# bluetooth.net
KiCad netlist of a schematic drawn in Altium Designer
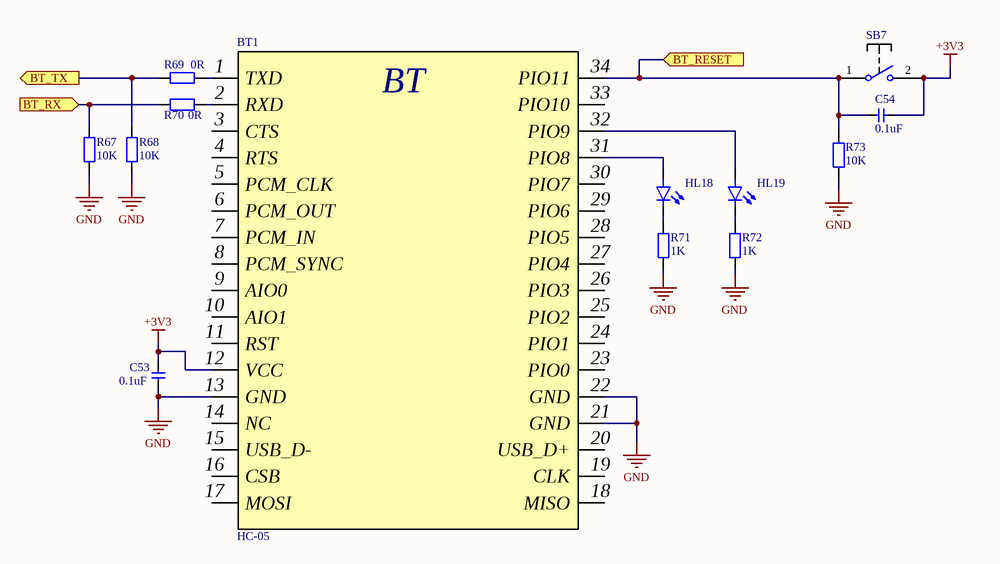
[diagram p0: bluetooth.SchDoc]

(export (version "E")
  (design (tool "Eeschema 10.0.6"))
  (components
    (comp (ref "BT1")
      (value "HC-05")
      (footprint "HC-05")
      (description "Bluetooth")
      (libsource (lib "Asterisk") (part "HC-05"))
    )
    (comp (ref "C53")
      (value "0.1uF")
      (footprint "CAP0805")
      (description "Ceramic SMD Cap")
      (libsource (lib "Asterisk") (part "CAP Ceramic"))
    )
    (comp (ref "C54")
      (value "0.1uF")
      (footprint "CAP0805")
      (description "Ceramic SMD Cap")
      (libsource (lib "Asterisk") (part "CAP Ceramic"))
    )
    (comp (ref "HL18")
      (value "White")
      (footprint "LED0603_WHITE")
      (description "SMD LED")
      (libsource (lib "Asterisk") (part "LED"))
    )
    (comp (ref "HL19")
      (value "White")
      (footprint "LED0603_WHITE")
      (description "SMD LED")
      (libsource (lib "Asterisk") (part "LED"))
    )
    (comp (ref "R67")
      (value "10K")
      (footprint "RES0805")
      (description "RES smd")
      (libsource (lib "Asterisk") (part "RES"))
    )
    (comp (ref "R68")
      (value "10K")
      (footprint "RES0805")
      (description "RES smd")
      (libsource (lib "Asterisk") (part "RES"))
    )
    (comp (ref "R69")
      (value "0R")
      (footprint "RES0805")
      (description "RES smd")
      (libsource (lib "Asterisk") (part "RES"))
    )
    (comp (ref "R70")
      (value "0R")
      (footprint "RES0805")
      (description "RES smd")
      (libsource (lib "Asterisk") (part "RES"))
    )
    (comp (ref "R71")
      (value "1K")
      (footprint "RES0805")
      (description "RES smd")
      (libsource (lib "Asterisk") (part "RES"))
    )
    (comp (ref "R72")
      (value "1K")
      (footprint "RES0805")
      (description "RES smd")
      (libsource (lib "Asterisk") (part "RES"))
    )
    (comp (ref "R73")
      (value "10K")
      (footprint "RES0805")
      (description "RES smd")
      (libsource (lib "Asterisk") (part "RES"))
    )
    (comp (ref "SB7")
      (value "TACT 6.0 X 3.5")
      (footprint "PTS636 SP43 LFS")
      (description "Button")
      (fields
        (field (name "PART NUMBER") "PTS636 SP43 LFS")
        (field (name "DIGI-KEY PART NUMBER") "CKN12304-ND")
      )
      (libsource (lib "SssAccesDatbase") (part "SW-SPST"))
    )
  )
  (nets
    (net (code "1") (name "+3V3") (class "Default")
      (node (ref "BT1") (pin "12") (pinfunction "VCC_12") (pintype "passive"))
      (node (ref "C53") (pin "2") (pinfunction "2_2") (pintype "passive"))
      (node (ref "C54") (pin "1") (pinfunction "1_1") (pintype "passive"))
      (node (ref "SB7") (pin "2") (pinfunction "NO_2") (pintype "passive"))
    )
    (net (code "2") (name "/BT_RESET") (class "Default")
      (node (ref "BT1") (pin "34") (pinfunction "PIO11_34") (pintype "passive"))
      (node (ref "C54") (pin "2") (pinfunction "2_2") (pintype "passive"))
      (node (ref "R73") (pin "2") (pinfunction "2_2") (pintype "passive"))
      (node (ref "SB7") (pin "1") (pinfunction "COMMON_1") (pintype "passive"))
    )
    (net (code "3") (name "/BT_RX") (class "Default")
      (node (ref "R67") (pin "2") (pinfunction "2_2") (pintype "passive"))
      (node (ref "R70") (pin "2") (pinfunction "2_2") (pintype "passive"))
    )
    (net (code "4") (name "/BT_TX") (class "Default")
      (node (ref "R68") (pin "2") (pinfunction "2_2") (pintype "passive"))
      (node (ref "R69") (pin "2") (pinfunction "2_2") (pintype "passive"))
    )
    (net (code "5") (name "GND") (class "Default")
      (node (ref "BT1") (pin "13") (pinfunction "GND_13") (pintype "passive"))
      (node (ref "BT1") (pin "21") (pinfunction "GND_21") (pintype "passive"))
      (node (ref "BT1") (pin "22") (pinfunction "GND_22") (pintype "passive"))
      (node (ref "C53") (pin "1") (pinfunction "1_1") (pintype "passive"))
      (node (ref "R67") (pin "1") (pinfunction "1_1") (pintype "passive"))
      (node (ref "R68") (pin "1") (pinfunction "1_1") (pintype "passive"))
      (node (ref "R71") (pin "1") (pinfunction "1_1") (pintype "passive"))
      (node (ref "R72") (pin "1") (pinfunction "1_1") (pintype "passive"))
      (node (ref "R73") (pin "1") (pinfunction "1_1") (pintype "passive"))
    )
    (net (code "6") (name "Net-(BT1-PIO8)") (class "Default")
      (node (ref "BT1") (pin "31") (pinfunction "PIO8_31") (pintype "passive"))
      (node (ref "HL18") (pin "2") (pinfunction "A_2") (pintype "passive"))
    )
    (net (code "7") (name "Net-(BT1-PIO9)") (class "Default")
      (node (ref "BT1") (pin "32") (pinfunction "PIO9_32") (pintype "passive"))
      (node (ref "HL19") (pin "2") (pinfunction "A_2") (pintype "passive"))
    )
    (net (code "8") (name "Net-(BT1-RXD)") (class "Default")
      (node (ref "BT1") (pin "2") (pinfunction "RXD_2") (pintype "passive"))
      (node (ref "R70") (pin "1") (pinfunction "1_1") (pintype "passive"))
    )
    (net (code "9") (name "Net-(BT1-TXD)") (class "Default")
      (node (ref "BT1") (pin "1") (pinfunction "TXD_1") (pintype "passive"))
      (node (ref "R69") (pin "1") (pinfunction "1_1") (pintype "passive"))
    )
    (net (code "10") (name "Net-(HL18-K)") (class "Default")
      (node (ref "HL18") (pin "1") (pinfunction "K_1") (pintype "passive"))
      (node (ref "R71") (pin "2") (pinfunction "2_2") (pintype "passive"))
    )
    (net (code "11") (name "Net-(HL19-K)") (class "Default")
      (node (ref "HL19") (pin "1") (pinfunction "K_1") (pintype "passive"))
      (node (ref "R72") (pin "2") (pinfunction "2_2") (pintype "passive"))
    )
    (net (code "12") (name "unconnected-(BT1-AIO0-Pad9)") (class "Default")
      (node (ref "BT1") (pin "9") (pinfunction "AIO0_9") (pintype "passive"))
    )
    (net (code "13") (name "unconnected-(BT1-AIO1-Pad10)") (class "Default")
      (node (ref "BT1") (pin "10") (pinfunction "AIO1_10") (pintype "passive"))
    )
    (net (code "14") (name "unconnected-(BT1-CLK-Pad19)") (class "Default")
      (node (ref "BT1") (pin "19") (pinfunction "CLK_19") (pintype "passive"))
    )
    (net (code "15") (name "unconnected-(BT1-CSB-Pad16)") (class "Default")
      (node (ref "BT1") (pin "16") (pinfunction "CSB_16") (pintype "passive"))
    )
    (net (code "16") (name "unconnected-(BT1-CTS-Pad3)") (class "Default")
      (node (ref "BT1") (pin "3") (pinfunction "CTS_3") (pintype "passive"))
    )
    (net (code "17") (name "unconnected-(BT1-MISO-Pad18)") (class "Default")
      (node (ref "BT1") (pin "18") (pinfunction "MISO_18") (pintype "passive"))
    )
    (net (code "18") (name "unconnected-(BT1-MOSI-Pad17)") (class "Default")
      (node (ref "BT1") (pin "17") (pinfunction "MOSI_17") (pintype "passive"))
    )
    (net (code "19") (name "unconnected-(BT1-NC-Pad14)") (class "Default")
      (node (ref "BT1") (pin "14") (pinfunction "NC_14") (pintype "passive"))
    )
    (net (code "20") (name "unconnected-(BT1-PCM_CLK-Pad5)") (class "Default")
      (node (ref "BT1") (pin "5") (pinfunction "PCM_CLK_5") (pintype "passive"))
    )
    (net (code "21") (name "unconnected-(BT1-PCM_IN-Pad7)") (class "Default")
      (node (ref "BT1") (pin "7") (pinfunction "PCM_IN_7") (pintype "passive"))
    )
    (net (code "22") (name "unconnected-(BT1-PCM_OUT-Pad6)") (class "Default")
      (node (ref "BT1") (pin "6") (pinfunction "PCM_OUT_6") (pintype "passive"))
    )
    (net (code "23") (name "unconnected-(BT1-PCM_SYNC-Pad8)") (class "Default")
      (node (ref "BT1") (pin "8") (pinfunction "PCM_SYNC_8") (pintype "passive"))
    )
    (net (code "24") (name "unconnected-(BT1-PIO0-Pad23)") (class "Default")
      (node (ref "BT1") (pin "23") (pinfunction "PIO0_23") (pintype "passive"))
    )
    (net (code "25") (name "unconnected-(BT1-PIO1-Pad24)") (class "Default")
      (node (ref "BT1") (pin "24") (pinfunction "PIO1_24") (pintype "passive"))
    )
    (net (code "26") (name "unconnected-(BT1-PIO2-Pad25)") (class "Default")
      (node (ref "BT1") (pin "25") (pinfunction "PIO2_25") (pintype "passive"))
    )
    (net (code "27") (name "unconnected-(BT1-PIO3-Pad26)") (class "Default")
      (node (ref "BT1") (pin "26") (pinfunction "PIO3_26") (pintype "passive"))
    )
    (net (code "28") (name "unconnected-(BT1-PIO4-Pad27)") (class "Default")
      (node (ref "BT1") (pin "27") (pinfunction "PIO4_27") (pintype "passive"))
    )
    (net (code "29") (name "unconnected-(BT1-PIO5-Pad28)") (class "Default")
      (node (ref "BT1") (pin "28") (pinfunction "PIO5_28") (pintype "passive"))
    )
    (net (code "30") (name "unconnected-(BT1-PIO6-Pad29)") (class "Default")
      (node (ref "BT1") (pin "29") (pinfunction "PIO6_29") (pintype "passive"))
    )
    (net (code "31") (name "unconnected-(BT1-PIO7-Pad30)") (class "Default")
      (node (ref "BT1") (pin "30") (pinfunction "PIO7_30") (pintype "passive"))
    )
    (net (code "32") (name "unconnected-(BT1-PIO10-Pad33)") (class "Default")
      (node (ref "BT1") (pin "33") (pinfunction "PIO10_33") (pintype "passive"))
    )
    (net (code "33") (name "unconnected-(BT1-RST-Pad11)") (class "Default")
      (node (ref "BT1") (pin "11") (pinfunction "RST_11") (pintype "passive"))
    )
    (net (code "34") (name "unconnected-(BT1-RTS-Pad4)") (class "Default")
      (node (ref "BT1") (pin "4") (pinfunction "RTS_4") (pintype "passive"))
    )
    (net (code "35") (name "unconnected-(BT1-USB_D+-Pad20)") (class "Default")
      (node (ref "BT1") (pin "20") (pinfunction "USB_D+_20") (pintype "passive"))
    )
    (net (code "36") (name "unconnected-(BT1-USB_D--Pad15)") (class "Default")
      (node (ref "BT1") (pin "15") (pinfunction "USB_D-_15") (pintype "passive"))
    )
  )
)
